# fiddle_old.net
KiCad netlist of a schematic drawn in EAGLE
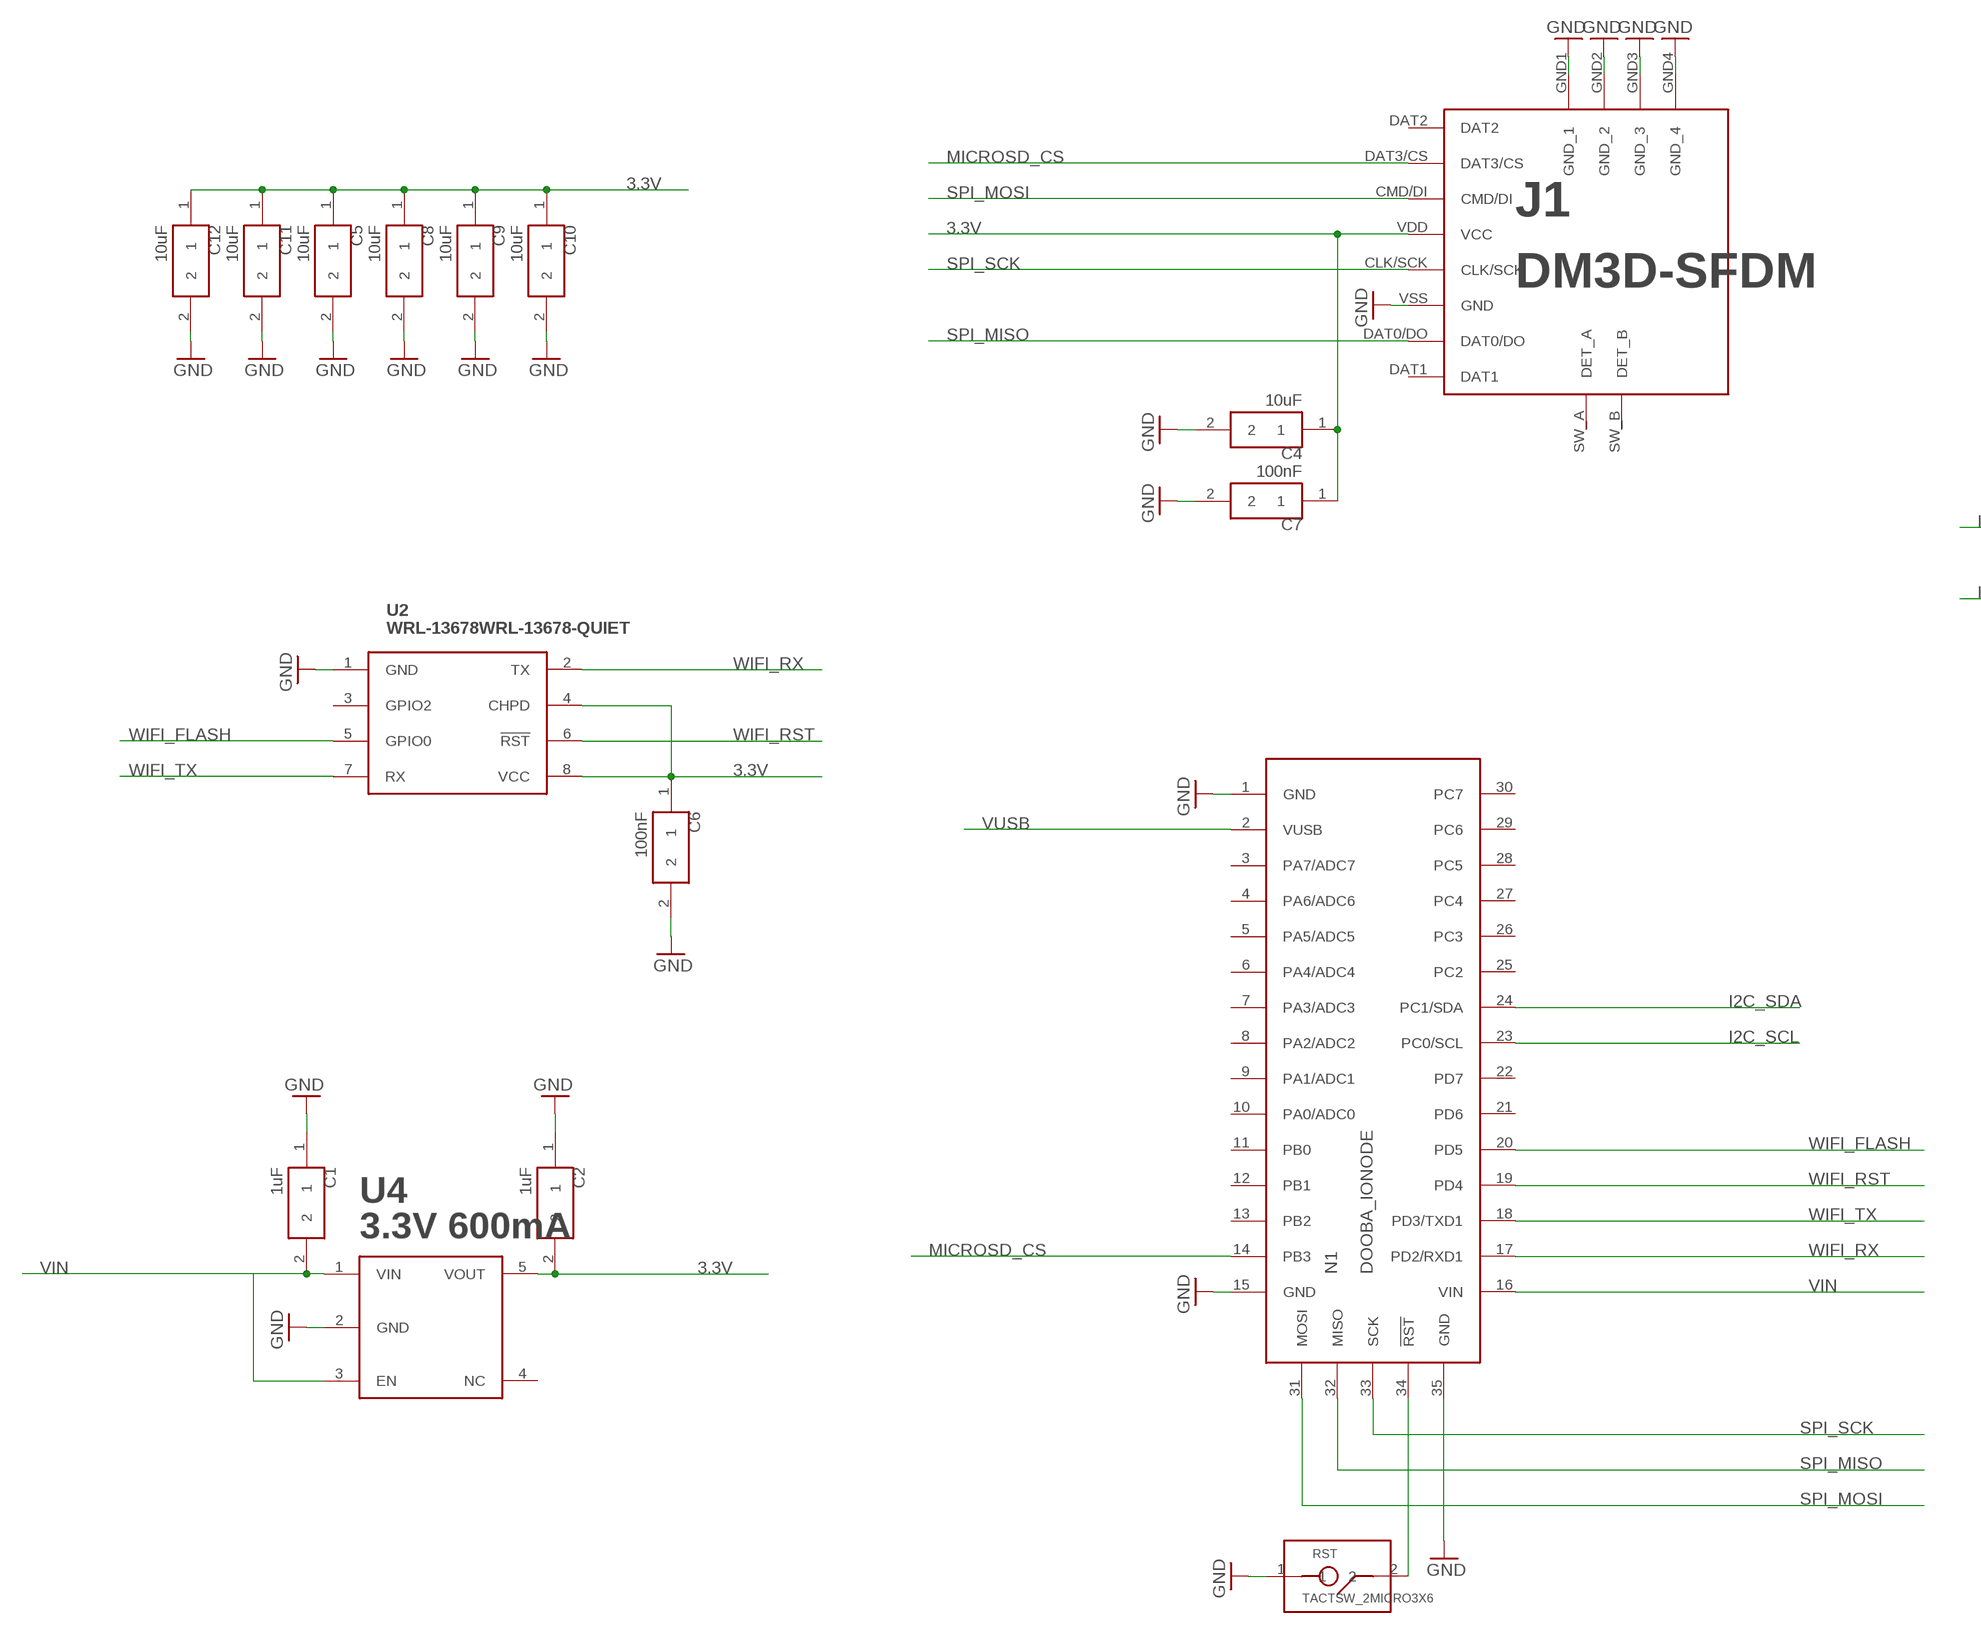
[diagram p0: schematic, sheet 1, part 1 of 2]
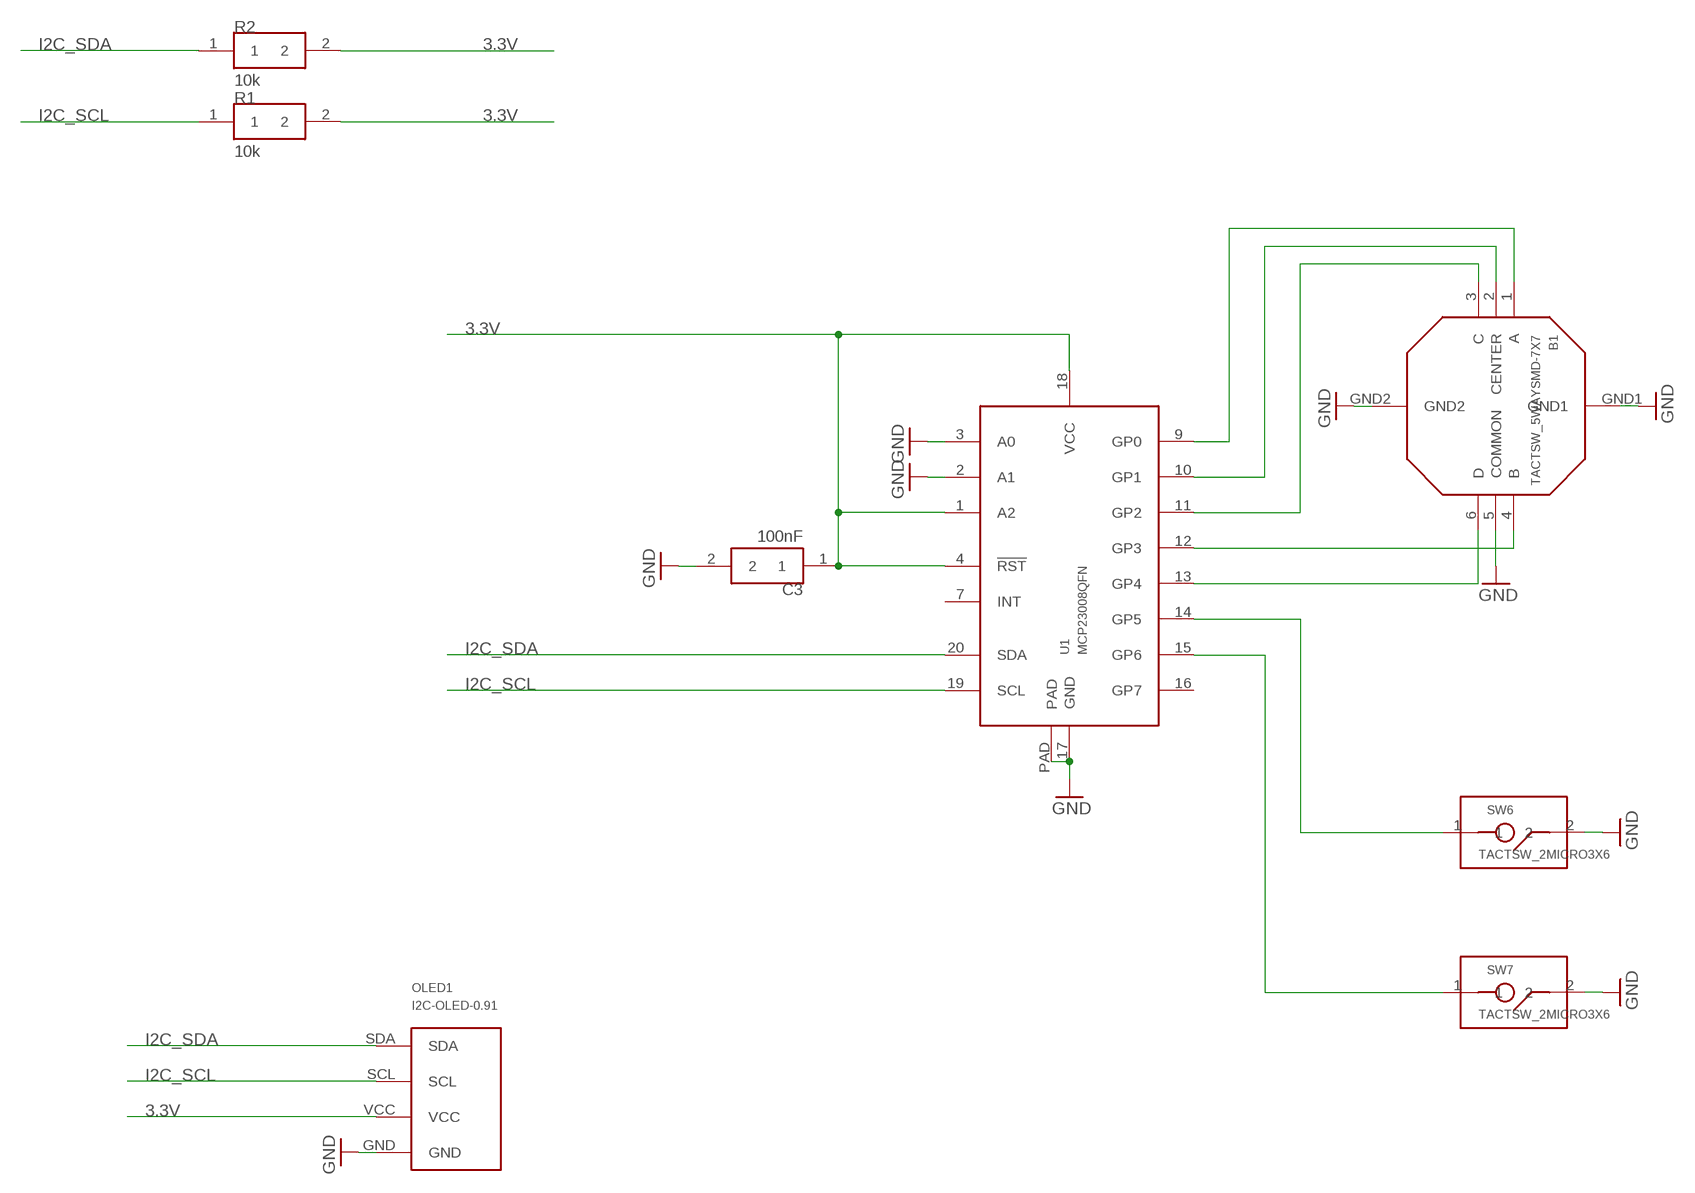
[diagram p1: schematic, sheet 1, part 2 of 2]

(export (version "E")
  (design (tool "Eeschema 10.0.6"))
  (components
    (comp (ref "B1")
      (value "TACTSW_5WAYSMD-7X7")
      (footprint "eagle-import:TACTSW-5WAY-7X7")
      (libsource (lib "eagle-import") (part "TACTSW_5WAYSMD-7X7"))
    )
    (comp (ref "C1")
      (value "1uF")
      (footprint "eagle-import:0805")
      (libsource (lib "eagle-import") (part "CAP0805"))
    )
    (comp (ref "C2")
      (value "1uF")
      (footprint "eagle-import:0805")
      (libsource (lib "eagle-import") (part "CAP0805"))
    )
    (comp (ref "C3")
      (value "100nF")
      (footprint "eagle-import:0805")
      (libsource (lib "eagle-import") (part "CAP0805"))
    )
    (comp (ref "C4")
      (value "10uF")
      (footprint "eagle-import:0805")
      (libsource (lib "eagle-import") (part "CAP0805"))
    )
    (comp (ref "C5")
      (value "10uF")
      (footprint "eagle-import:0805")
      (libsource (lib "eagle-import") (part "CAP0805"))
    )
    (comp (ref "C6")
      (value "100nF")
      (footprint "eagle-import:0805")
      (libsource (lib "eagle-import") (part "CAP0805"))
    )
    (comp (ref "C7")
      (value "100nF")
      (footprint "eagle-import:0805")
      (libsource (lib "eagle-import") (part "CAP0805"))
    )
    (comp (ref "C8")
      (value "10uF")
      (footprint "eagle-import:0805")
      (libsource (lib "eagle-import") (part "CAP0805"))
    )
    (comp (ref "C9")
      (value "10uF")
      (footprint "eagle-import:0805")
      (libsource (lib "eagle-import") (part "CAP0805"))
    )
    (comp (ref "C10")
      (value "10uF")
      (footprint "eagle-import:0805")
      (libsource (lib "eagle-import") (part "CAP0805"))
    )
    (comp (ref "C11")
      (value "10uF")
      (footprint "eagle-import:0805")
      (libsource (lib "eagle-import") (part "CAP0805"))
    )
    (comp (ref "C12")
      (value "10uF")
      (footprint "eagle-import:0805")
      (libsource (lib "eagle-import") (part "CAP0805"))
    )
    (comp (ref "J1")
      (value "DM3D-SFDM")
      (footprint "eagle-import:DM3D-SF")
      (libsource (lib "eagle-import") (part "DM3D-SFDM"))
    )
    (comp (ref "N1")
      (value "DOOBA_IONODE")
      (footprint "eagle-import:DOOBA_IONODE")
      (libsource (lib "eagle-import") (part "DOOBA_IONODE"))
    )
    (comp (ref "OLED1")
      (value "I2C-OLED-0.91")
      (footprint "eagle-import:I2C-OLED-0.91")
      (libsource (lib "eagle-import") (part "I2C-OLED-0.91"))
    )
    (comp (ref "R1")
      (value "10k")
      (footprint "eagle-import:0805")
      (libsource (lib "eagle-import") (part "RES0805"))
    )
    (comp (ref "R2")
      (value "10k")
      (footprint "eagle-import:0805")
      (libsource (lib "eagle-import") (part "RES0805"))
    )
    (comp (ref "RST")
      (value "TACTSW_2MICRO3X6")
      (footprint "eagle-import:TACTSW_MICRO3X6")
      (libsource (lib "eagle-import") (part "TACTSW_2MICRO3X6"))
    )
    (comp (ref "SW6")
      (value "TACTSW_2MICRO3X6")
      (footprint "eagle-import:TACTSW_MICRO3X6")
      (libsource (lib "eagle-import") (part "TACTSW_2MICRO3X6"))
    )
    (comp (ref "SW7")
      (value "TACTSW_2MICRO3X6")
      (footprint "eagle-import:TACTSW_MICRO3X6")
      (libsource (lib "eagle-import") (part "TACTSW_2MICRO3X6"))
    )
    (comp (ref "U1")
      (value "MCP23008QFN")
      (footprint "eagle-import:20-VQFN")
      (libsource (lib "eagle-import") (part "MCP23008QFN"))
    )
    (comp (ref "U2")
      (value "WRL-13678WRL-13678-QUIET")
      (footprint "eagle-import:WRL-13678-QUIET")
      (libsource (lib "eagle-import") (part "WRL-13678WRL-13678-QUIET"))
    )
    (comp (ref "U4")
      (value "3.3V 600mA")
      (footprint "eagle-import:SOT23-5")
      (libsource (lib "eagle-import") (part "LP3985SOT23-5"))
    )
  )
  (nets
    (net (code "1") (name "/3.3V") (class "Default")
      (node (ref "C10") (pin "1") (pinfunction "1_1") (pintype "bidirectional"))
      (node (ref "C11") (pin "1") (pinfunction "1_1") (pintype "bidirectional"))
      (node (ref "C12") (pin "1") (pinfunction "1_1") (pintype "bidirectional"))
      (node (ref "C2") (pin "2") (pinfunction "2_2") (pintype "bidirectional"))
      (node (ref "C3") (pin "1") (pinfunction "1_1") (pintype "bidirectional"))
      (node (ref "C4") (pin "1") (pinfunction "1_1") (pintype "bidirectional"))
      (node (ref "C5") (pin "1") (pinfunction "1_1") (pintype "bidirectional"))
      (node (ref "C6") (pin "1") (pinfunction "1_1") (pintype "bidirectional"))
      (node (ref "C7") (pin "1") (pinfunction "1_1") (pintype "bidirectional"))
      (node (ref "C8") (pin "1") (pinfunction "1_1") (pintype "bidirectional"))
      (node (ref "C9") (pin "1") (pinfunction "1_1") (pintype "bidirectional"))
      (node (ref "J1") (pin "VDD") (pinfunction "VCC_VDD") (pintype "bidirectional"))
      (node (ref "OLED1") (pin "VCC") (pinfunction "VCC_VCC") (pintype "bidirectional"))
      (node (ref "R1") (pin "2") (pinfunction "2_2") (pintype "bidirectional"))
      (node (ref "R2") (pin "2") (pinfunction "2_2") (pintype "bidirectional"))
      (node (ref "U1") (pin "1") (pinfunction "A2_1") (pintype "bidirectional"))
      (node (ref "U1") (pin "18") (pinfunction "VCC_18") (pintype "bidirectional"))
      (node (ref "U1") (pin "4") (pinfunction "~{RST}_4") (pintype "bidirectional"))
      (node (ref "U2") (pin "4") (pinfunction "CHPD_4") (pintype "bidirectional"))
      (node (ref "U2") (pin "8") (pinfunction "VCC_8") (pintype "bidirectional"))
      (node (ref "U4") (pin "5") (pinfunction "VOUT_5") (pintype "bidirectional"))
    )
    (net (code "2") (name "/I2C_SCL") (class "Default")
      (node (ref "N1") (pin "23") (pinfunction "PC0/SCL_23") (pintype "bidirectional"))
      (node (ref "OLED1") (pin "SCL") (pinfunction "SCL_SCL") (pintype "bidirectional"))
      (node (ref "R1") (pin "1") (pinfunction "1_1") (pintype "bidirectional"))
      (node (ref "U1") (pin "19") (pinfunction "SCL_19") (pintype "bidirectional"))
    )
    (net (code "3") (name "/I2C_SDA") (class "Default")
      (node (ref "N1") (pin "24") (pinfunction "PC1/SDA_24") (pintype "bidirectional"))
      (node (ref "OLED1") (pin "SDA") (pinfunction "SDA_SDA") (pintype "bidirectional"))
      (node (ref "R2") (pin "1") (pinfunction "1_1") (pintype "bidirectional"))
      (node (ref "U1") (pin "20") (pinfunction "SDA_20") (pintype "bidirectional"))
    )
    (net (code "4") (name "/MICROSD_CS") (class "Default")
      (node (ref "J1") (pin "DAT3/CS") (pinfunction "DAT3/CS_DAT3/CS") (pintype "bidirectional"))
      (node (ref "N1") (pin "14") (pinfunction "PB3_14") (pintype "bidirectional"))
    )
    (net (code "5") (name "/SPI_MISO") (class "Default")
      (node (ref "J1") (pin "DAT0/DO") (pinfunction "DAT0/DO_DAT0/DO") (pintype "bidirectional"))
      (node (ref "N1") (pin "32") (pinfunction "MISO_32") (pintype "bidirectional"))
    )
    (net (code "6") (name "/SPI_MOSI") (class "Default")
      (node (ref "J1") (pin "CMD/DI") (pinfunction "CMD/DI_CMD/DI") (pintype "bidirectional"))
      (node (ref "N1") (pin "31") (pinfunction "MOSI_31") (pintype "bidirectional"))
    )
    (net (code "7") (name "/SPI_SCK") (class "Default")
      (node (ref "J1") (pin "CLK/SCK") (pinfunction "CLK/SCK_CLK/SCK") (pintype "bidirectional"))
      (node (ref "N1") (pin "33") (pinfunction "SCK_33") (pintype "bidirectional"))
    )
    (net (code "8") (name "/VIN") (class "Default")
      (node (ref "C1") (pin "2") (pinfunction "2_2") (pintype "bidirectional"))
      (node (ref "N1") (pin "16") (pinfunction "VIN_16") (pintype "bidirectional"))
      (node (ref "U4") (pin "1") (pinfunction "VIN_1") (pintype "bidirectional"))
      (node (ref "U4") (pin "3") (pinfunction "EN_3") (pintype "bidirectional"))
    )
    (net (code "9") (name "/VUSB") (class "Default")
      (node (ref "N1") (pin "2") (pinfunction "VUSB_2") (pintype "bidirectional"))
    )
    (net (code "10") (name "/WIFI_FLASH") (class "Default")
      (node (ref "N1") (pin "20") (pinfunction "PD5_20") (pintype "bidirectional"))
      (node (ref "U2") (pin "5") (pinfunction "GPIO0_5") (pintype "bidirectional"))
    )
    (net (code "11") (name "/WIFI_RST") (class "Default")
      (node (ref "N1") (pin "19") (pinfunction "PD4_19") (pintype "bidirectional"))
      (node (ref "U2") (pin "6") (pinfunction "~{RST}_6") (pintype "bidirectional"))
    )
    (net (code "12") (name "/WIFI_RX") (class "Default")
      (node (ref "N1") (pin "17") (pinfunction "PD2/RXD1_17") (pintype "bidirectional"))
      (node (ref "U2") (pin "2") (pinfunction "TX_2") (pintype "bidirectional"))
    )
    (net (code "13") (name "/WIFI_TX") (class "Default")
      (node (ref "N1") (pin "18") (pinfunction "PD3/TXD1_18") (pintype "bidirectional"))
      (node (ref "U2") (pin "7") (pinfunction "RX_7") (pintype "bidirectional"))
    )
    (net (code "14") (name "GND") (class "Default")
      (node (ref "B1") (pin "5") (pinfunction "COMMON_5") (pintype "bidirectional"))
      (node (ref "B1") (pin "GND1") (pinfunction "GND1_GND1") (pintype "bidirectional"))
      (node (ref "B1") (pin "GND2") (pinfunction "GND2_GND2") (pintype "bidirectional"))
      (node (ref "C1") (pin "1") (pinfunction "1_1") (pintype "bidirectional"))
      (node (ref "C10") (pin "2") (pinfunction "2_2") (pintype "bidirectional"))
      (node (ref "C11") (pin "2") (pinfunction "2_2") (pintype "bidirectional"))
      (node (ref "C12") (pin "2") (pinfunction "2_2") (pintype "bidirectional"))
      (node (ref "C2") (pin "1") (pinfunction "1_1") (pintype "bidirectional"))
      (node (ref "C3") (pin "2") (pinfunction "2_2") (pintype "bidirectional"))
      (node (ref "C4") (pin "2") (pinfunction "2_2") (pintype "bidirectional"))
      (node (ref "C5") (pin "2") (pinfunction "2_2") (pintype "bidirectional"))
      (node (ref "C6") (pin "2") (pinfunction "2_2") (pintype "bidirectional"))
      (node (ref "C7") (pin "2") (pinfunction "2_2") (pintype "bidirectional"))
      (node (ref "C8") (pin "2") (pinfunction "2_2") (pintype "bidirectional"))
      (node (ref "C9") (pin "2") (pinfunction "2_2") (pintype "bidirectional"))
      (node (ref "J1") (pin "GND1") (pinfunction "GND_1_GND1") (pintype "bidirectional"))
      (node (ref "J1") (pin "GND2") (pinfunction "GND_2_GND2") (pintype "bidirectional"))
      (node (ref "J1") (pin "GND3") (pinfunction "GND_3_GND3") (pintype "bidirectional"))
      (node (ref "J1") (pin "GND4") (pinfunction "GND_4_GND4") (pintype "bidirectional"))
      (node (ref "J1") (pin "VSS") (pinfunction "GND_VSS") (pintype "bidirectional"))
      (node (ref "N1") (pin "1") (pinfunction "GND_1") (pintype "bidirectional"))
      (node (ref "N1") (pin "15") (pinfunction "GND_15") (pintype "bidirectional"))
      (node (ref "N1") (pin "35") (pinfunction "GND_35") (pintype "bidirectional"))
      (node (ref "OLED1") (pin "GND") (pinfunction "GND_GND") (pintype "bidirectional"))
      (node (ref "RST") (pin "1") (pinfunction "1_1") (pintype "bidirectional"))
      (node (ref "SW6") (pin "2") (pinfunction "2_2") (pintype "bidirectional"))
      (node (ref "SW7") (pin "2") (pinfunction "2_2") (pintype "bidirectional"))
      (node (ref "U1") (pin "17") (pinfunction "GND_17") (pintype "bidirectional"))
      (node (ref "U1") (pin "2") (pinfunction "A1_2") (pintype "bidirectional"))
      (node (ref "U1") (pin "3") (pinfunction "A0_3") (pintype "bidirectional"))
      (node (ref "U1") (pin "PAD") (pinfunction "PAD_PAD") (pintype "bidirectional"))
      (node (ref "U2") (pin "1") (pinfunction "GND_1") (pintype "bidirectional"))
      (node (ref "U4") (pin "2") (pinfunction "GND_2") (pintype "bidirectional"))
    )
    (net (code "15") (name "Net-(B1-A)") (class "Default")
      (node (ref "B1") (pin "1") (pinfunction "A_1") (pintype "bidirectional"))
      (node (ref "U1") (pin "9") (pinfunction "GP0_9") (pintype "bidirectional"))
    )
    (net (code "16") (name "Net-(B1-B)") (class "Default")
      (node (ref "B1") (pin "4") (pinfunction "B_4") (pintype "bidirectional"))
      (node (ref "U1") (pin "12") (pinfunction "GP3_12") (pintype "bidirectional"))
    )
    (net (code "17") (name "Net-(B1-C)") (class "Default")
      (node (ref "B1") (pin "3") (pinfunction "C_3") (pintype "bidirectional"))
      (node (ref "U1") (pin "11") (pinfunction "GP2_11") (pintype "bidirectional"))
    )
    (net (code "18") (name "Net-(B1-CENTER)") (class "Default")
      (node (ref "B1") (pin "2") (pinfunction "CENTER_2") (pintype "bidirectional"))
      (node (ref "U1") (pin "10") (pinfunction "GP1_10") (pintype "bidirectional"))
    )
    (net (code "19") (name "Net-(B1-D)") (class "Default")
      (node (ref "B1") (pin "6") (pinfunction "D_6") (pintype "bidirectional"))
      (node (ref "U1") (pin "13") (pinfunction "GP4_13") (pintype "bidirectional"))
    )
    (net (code "20") (name "Net-(N1-~{RST})") (class "Default")
      (node (ref "N1") (pin "34") (pinfunction "~{RST}_34") (pintype "bidirectional"))
      (node (ref "RST") (pin "2") (pinfunction "2_2") (pintype "bidirectional"))
    )
    (net (code "21") (name "Net-(U1-GP5)") (class "Default")
      (node (ref "SW6") (pin "1") (pinfunction "1_1") (pintype "bidirectional"))
      (node (ref "U1") (pin "14") (pinfunction "GP5_14") (pintype "bidirectional"))
    )
    (net (code "22") (name "Net-(U1-GP6)") (class "Default")
      (node (ref "SW7") (pin "1") (pinfunction "1_1") (pintype "bidirectional"))
      (node (ref "U1") (pin "15") (pinfunction "GP6_15") (pintype "bidirectional"))
    )
    (net (code "23") (name "unconnected-(J1-DET_A-PadSW_A)") (class "Default")
      (node (ref "J1") (pin "SW_A") (pinfunction "DET_A_SW_A") (pintype "bidirectional"))
    )
    (net (code "24") (name "unconnected-(J1-DET_B-PadSW_B)") (class "Default")
      (node (ref "J1") (pin "SW_B") (pinfunction "DET_B_SW_B") (pintype "bidirectional"))
    )
    (net (code "25") (name "unconnected-(J1-PadDAT1)") (class "Default")
      (node (ref "J1") (pin "DAT1") (pinfunction "DAT1_DAT1") (pintype "bidirectional"))
    )
    (net (code "26") (name "unconnected-(J1-PadDAT2)") (class "Default")
      (node (ref "J1") (pin "DAT2") (pinfunction "DAT2_DAT2") (pintype "bidirectional"))
    )
    (net (code "27") (name "unconnected-(N1-PA0{slash}ADC0-Pad10)") (class "Default")
      (node (ref "N1") (pin "10") (pinfunction "PA0/ADC0_10") (pintype "bidirectional"))
    )
    (net (code "28") (name "unconnected-(N1-PA1{slash}ADC1-Pad9)") (class "Default")
      (node (ref "N1") (pin "9") (pinfunction "PA1/ADC1_9") (pintype "bidirectional"))
    )
    (net (code "29") (name "unconnected-(N1-PA2{slash}ADC2-Pad8)") (class "Default")
      (node (ref "N1") (pin "8") (pinfunction "PA2/ADC2_8") (pintype "bidirectional"))
    )
    (net (code "30") (name "unconnected-(N1-PA3{slash}ADC3-Pad7)") (class "Default")
      (node (ref "N1") (pin "7") (pinfunction "PA3/ADC3_7") (pintype "bidirectional"))
    )
    (net (code "31") (name "unconnected-(N1-PA4{slash}ADC4-Pad6)") (class "Default")
      (node (ref "N1") (pin "6") (pinfunction "PA4/ADC4_6") (pintype "bidirectional"))
    )
    (net (code "32") (name "unconnected-(N1-PA5{slash}ADC5-Pad5)") (class "Default")
      (node (ref "N1") (pin "5") (pinfunction "PA5/ADC5_5") (pintype "bidirectional"))
    )
    (net (code "33") (name "unconnected-(N1-PA6{slash}ADC6-Pad4)") (class "Default")
      (node (ref "N1") (pin "4") (pinfunction "PA6/ADC6_4") (pintype "bidirectional"))
    )
    (net (code "34") (name "unconnected-(N1-PA7{slash}ADC7-Pad3)") (class "Default")
      (node (ref "N1") (pin "3") (pinfunction "PA7/ADC7_3") (pintype "bidirectional"))
    )
    (net (code "35") (name "unconnected-(N1-PB0-Pad11)") (class "Default")
      (node (ref "N1") (pin "11") (pinfunction "PB0_11") (pintype "bidirectional"))
    )
    (net (code "36") (name "unconnected-(N1-PB1-Pad12)") (class "Default")
      (node (ref "N1") (pin "12") (pinfunction "PB1_12") (pintype "bidirectional"))
    )
    (net (code "37") (name "unconnected-(N1-PB2-Pad13)") (class "Default")
      (node (ref "N1") (pin "13") (pinfunction "PB2_13") (pintype "bidirectional"))
    )
    (net (code "38") (name "unconnected-(N1-PC2-Pad25)") (class "Default")
      (node (ref "N1") (pin "25") (pinfunction "PC2_25") (pintype "bidirectional"))
    )
    (net (code "39") (name "unconnected-(N1-PC3-Pad26)") (class "Default")
      (node (ref "N1") (pin "26") (pinfunction "PC3_26") (pintype "bidirectional"))
    )
    (net (code "40") (name "unconnected-(N1-PC4-Pad27)") (class "Default")
      (node (ref "N1") (pin "27") (pinfunction "PC4_27") (pintype "bidirectional"))
    )
    (net (code "41") (name "unconnected-(N1-PC5-Pad28)") (class "Default")
      (node (ref "N1") (pin "28") (pinfunction "PC5_28") (pintype "bidirectional"))
    )
    (net (code "42") (name "unconnected-(N1-PC6-Pad29)") (class "Default")
      (node (ref "N1") (pin "29") (pinfunction "PC6_29") (pintype "bidirectional"))
    )
    (net (code "43") (name "unconnected-(N1-PC7-Pad30)") (class "Default")
      (node (ref "N1") (pin "30") (pinfunction "PC7_30") (pintype "bidirectional"))
    )
    (net (code "44") (name "unconnected-(N1-PD6-Pad21)") (class "Default")
      (node (ref "N1") (pin "21") (pinfunction "PD6_21") (pintype "bidirectional"))
    )
    (net (code "45") (name "unconnected-(N1-PD7-Pad22)") (class "Default")
      (node (ref "N1") (pin "22") (pinfunction "PD7_22") (pintype "bidirectional"))
    )
    (net (code "46") (name "unconnected-(U1-GP7-Pad16)") (class "Default")
      (node (ref "U1") (pin "16") (pinfunction "GP7_16") (pintype "bidirectional"))
    )
    (net (code "47") (name "unconnected-(U1-INT-Pad7)") (class "Default")
      (node (ref "U1") (pin "7") (pinfunction "INT_7") (pintype "bidirectional"))
    )
    (net (code "48") (name "unconnected-(U2-GPIO2-Pad3)") (class "Default")
      (node (ref "U2") (pin "3") (pinfunction "GPIO2_3") (pintype "bidirectional"))
    )
    (net (code "49") (name "unconnected-(U4-NC-Pad4)") (class "Default")
      (node (ref "U4") (pin "4") (pinfunction "NC_4") (pintype "bidirectional"))
    )
  )
)
